# Alim_Ticketing_Slave.net
KiCad netlist of a schematic drawn in Altium Designer
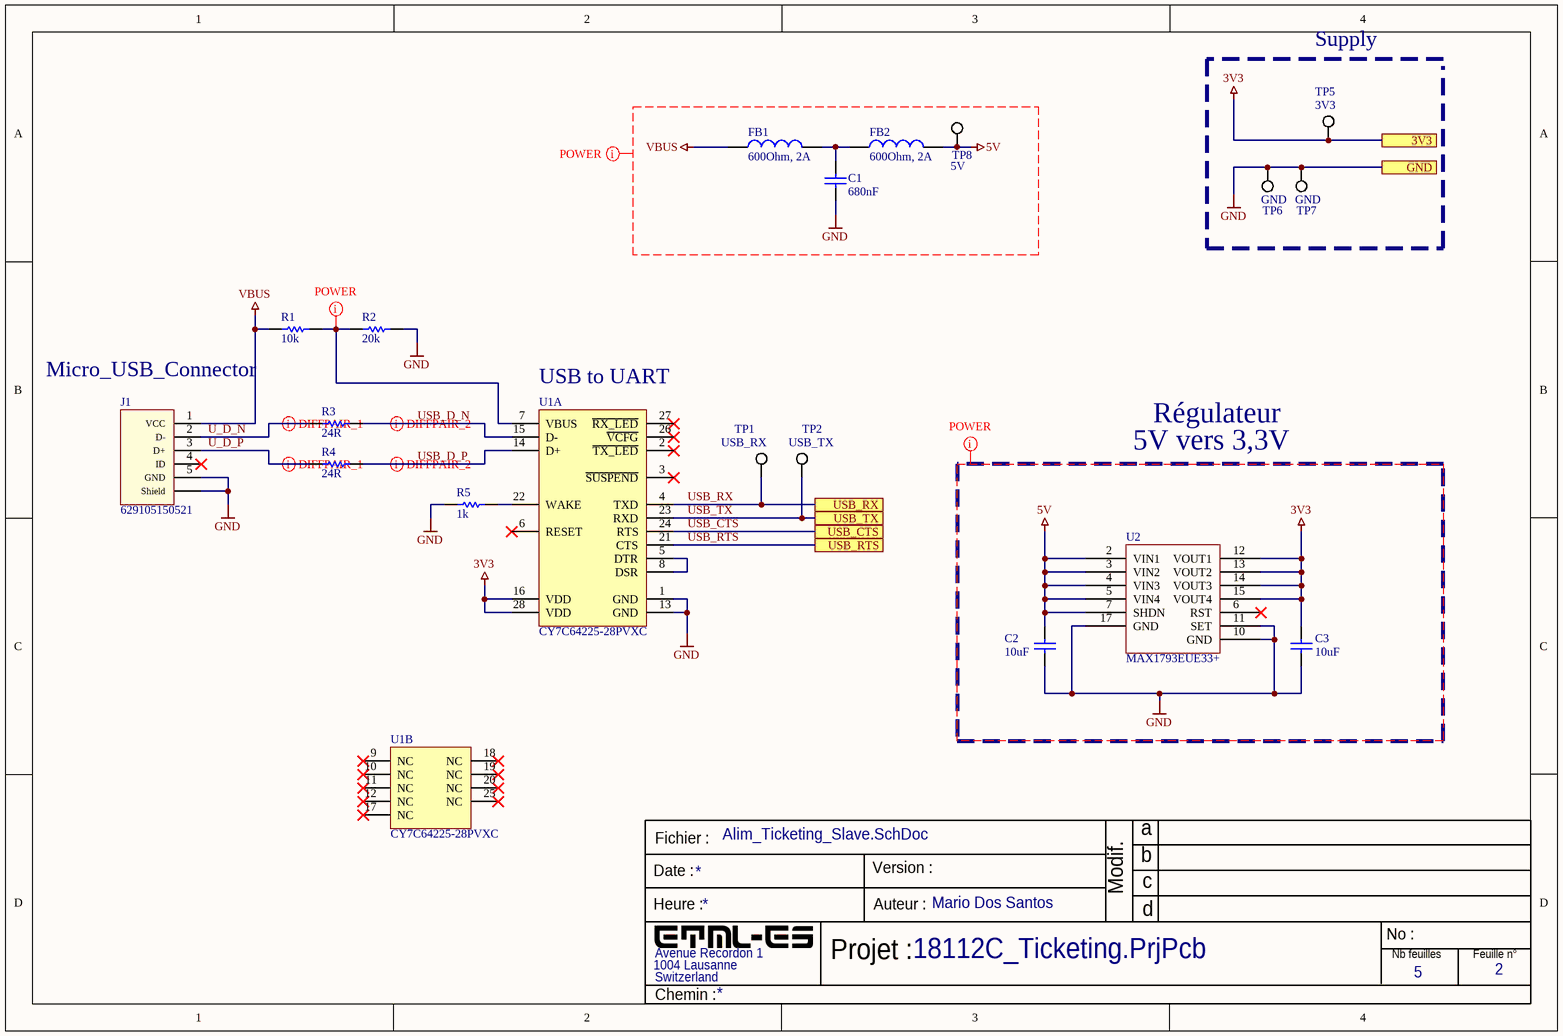
[diagram p0: Alim_Ticketing_Slave.SchDoc]

(export (version "E")
  (design (tool "Eeschema 10.0.6"))
  (components
    (comp (ref "C1")
      (value "680nF")
      (footprint "6-0805_N")
      (description "WCAP-CSGP General Purpose Ceramic Capacitors, size 0805, 100nF, +/-10%, 50VDC")
      (libsource (lib "VPA_v2b") (part "885012207098"))
    )
    (comp (ref "C2")
      (value "10uF")
      (footprint "6-0805_N")
      (description "Capacitor")
      (fields (field (name "PUBLISHER") "Altium Limited"))
      (libsource (lib "Miscellaneous Devices") (part "Cap"))
    )
    (comp (ref "C3")
      (value "10uF")
      (footprint "6-0805_N")
      (description "Capacitor")
      (fields (field (name "PUBLISHER") "Altium Limited"))
      (libsource (lib "Miscellaneous Devices") (part "Cap"))
    )
    (comp (ref "FB1")
      (value "600Ohm, 2A")
      (footprint "WE-CBF_0805_High Current")
      (description "WE-CBF SMT EMI Suppression Ferrite Bead, size 0805, 600Ohm, 2A")
      (fields (field (name "PART NUMBER") "742792040") (field (name "PUBLISHER") "Wurth Elektronik"))
      (libsource (lib "VPA_v2b") (part "742792040"))
    )
    (comp (ref "FB2")
      (value "600Ohm, 2A")
      (footprint "WE-CBF_0805_High Current")
      (description "WE-CBF SMT EMI Suppression Ferrite Bead, size 0805, 600Ohm, 2A")
      (fields (field (name "PART NUMBER") "742792040") (field (name "PUBLISHER") "Wurth Elektronik"))
      (libsource (lib "VPA_v2b") (part "742792040"))
    )
    (comp (ref "J1")
      (value "629105150521")
      (footprint "629105150521")
      (description "Micro USB 2.0 SMT Type B Horizontal 5 Contacts High Current WR-COM")
      (fields (field (name "PART NUMBER") "732-5960-1-ND") (field (name "PUBLISHER") "Wurth Elektronik"))
      (libsource (lib "PCB_Ticketing_Slave") (part "629105150521"))
    )
    (comp (ref "R1")
      (value "10k")
      (footprint "RESC0805(2012)_L")
      (description "100K 0.125W 5% 0805 (2012 Metric)  SMD")
      (fields (field (name "TOLERANCE") "5 %") (field (name "POWER") "0.125 W"))
      (libsource (lib "Altium Content Vault") (part "CMP-1013-00122-1"))
    )
    (comp (ref "R2")
      (value "20k")
      (footprint "RESC0805(2012)_L")
      (description "100K 0.125W 5% 0805 (2012 Metric)  SMD")
      (fields (field (name "TOLERANCE") "5 %") (field (name "POWER") "0.125 W"))
      (libsource (lib "Altium Content Vault") (part "CMP-1013-00122-1"))
    )
    (comp (ref "R3")
      (value "24R")
      (footprint "RESC0805(2012)_L")
      (description "100K 0.125W 5% 0805 (2012 Metric)  SMD")
      (fields (field (name "TOLERANCE") "5 %") (field (name "POWER") "0.125 W"))
      (libsource (lib "Altium Content Vault") (part "CMP-1013-00122-1"))
    )
    (comp (ref "R4")
      (value "24R")
      (footprint "RESC0805(2012)_L")
      (description "100K 0.125W 5% 0805 (2012 Metric)  SMD")
      (fields (field (name "TOLERANCE") "5 %") (field (name "POWER") "0.125 W"))
      (libsource (lib "Altium Content Vault") (part "CMP-1013-00122-1"))
    )
    (comp (ref "R5")
      (value "1k")
      (footprint "RESC0805(2012)_L")
      (description "100K 0.125W 5% 0805 (2012 Metric)  SMD")
      (fields (field (name "TOLERANCE") "5 %") (field (name "POWER") "0.125 W"))
      (libsource (lib "Altium Content Vault") (part "CMP-1013-00122-1"))
    )
    (comp (ref "TP1")
      (value "~")
      (footprint "KSTN-5019_V")
      (description "Test Point, 1 Position SMD, RoHS, Tape and Reel")
      (libsource (lib "Altium Content Vault") (part "TESTPOINT_WHITE"))
    )
    (comp (ref "TP2")
      (value "~")
      (footprint "KSTN-5019_V")
      (description "Test Point, 1 Position SMD, RoHS, Tape and Reel")
      (libsource (lib "Altium Content Vault") (part "TESTPOINT_WHITE"))
    )
    (comp (ref "TP5")
      (value "~")
      (footprint "KSTN-5019_V")
      (description "Test Point, 1 Position SMD, RoHS, Tape and Reel")
      (libsource (lib "Altium Content Vault") (part "TESTPOINT_WHITE"))
    )
    (comp (ref "TP6")
      (value "~")
      (footprint "KSTN-5019_V")
      (description "Test Point, 1 Position SMD, RoHS, Tape and Reel")
      (libsource (lib "Altium Content Vault") (part "TESTPOINT_WHITE"))
    )
    (comp (ref "TP7")
      (value "~")
      (footprint "KSTN-5019_V")
      (description "Test Point, 1 Position SMD, RoHS, Tape and Reel")
      (libsource (lib "Altium Content Vault") (part "TESTPOINT_WHITE"))
    )
    (comp (ref "TP8")
      (value "~")
      (footprint "KSTN-5019_V")
      (description "Test Point, 1 Position SMD, RoHS, Tape and Reel")
      (libsource (lib "Altium Content Vault") (part "TESTPOINT_WHITE"))
    )
    (comp (ref "U1")
      (value "CY7C64225-28PVXC")
      (footprint "CYP-PVX28_N")
      (description "USB-to-UART Bridge Controller, 3 to 5.25 V, 0 to 70 degC, 28-Pin SSOP (PVX28), Tube")
      (fields (field (name "MANUFACTURER") "Cypress") (field (name "PART NUMBER") "428-3158-ND"))
      (libsource (lib "PCB_Ticketing_Slave") (part "CMP-0967-00143-1"))
    )
    (comp (ref "U2")
      (value "MAX1793EUE33+")
      (footprint "TSOP65P640X110_HS-17N")
      (libsource (lib "2018A_CarteIoEscapeRoom_CAD") (part "MAX1793"))
    )
  )
  (nets
    (net (code "1") (name "/USB_CTS") (class "Default")
      (node (ref "U1") (pin "24") (pinfunction "RTS_24") (pintype "passive"))
    )
    (net (code "2") (name "/USB_D_N") (class "Default")
      (node (ref "R3") (pin "2") (pinfunction "2_2") (pintype "passive"))
      (node (ref "U1") (pin "15") (pinfunction "D-_15") (pintype "passive"))
    )
    (net (code "3") (name "/USB_D_P") (class "Default")
      (node (ref "R4") (pin "2") (pinfunction "2_2") (pintype "passive"))
      (node (ref "U1") (pin "14") (pinfunction "D+_14") (pintype "passive"))
    )
    (net (code "4") (name "/USB_RTS") (class "Default")
      (node (ref "U1") (pin "21") (pinfunction "CTS_21") (pintype "passive"))
    )
    (net (code "5") (name "/USB_RX") (class "Default")
      (node (ref "TP1") (pin "1") (pinfunction "1_1") (pintype "passive"))
      (node (ref "U1") (pin "4") (pinfunction "TXD_4") (pintype "passive"))
    )
    (net (code "6") (name "/USB_TX") (class "Default")
      (node (ref "TP2") (pin "1") (pinfunction "1_1") (pintype "passive"))
      (node (ref "U1") (pin "23") (pinfunction "RXD_23") (pintype "passive"))
    )
    (net (code "7") (name "/U_D_N") (class "Default")
      (node (ref "J1") (pin "2") (pinfunction "D-_2") (pintype "passive"))
      (node (ref "R3") (pin "1") (pinfunction "1_1") (pintype "passive"))
    )
    (net (code "8") (name "/U_D_P") (class "Default")
      (node (ref "J1") (pin "3") (pinfunction "D+_3") (pintype "passive"))
      (node (ref "R4") (pin "1") (pinfunction "1_1") (pintype "passive"))
    )
    (net (code "9") (name "3V3") (class "Default")
      (node (ref "C3") (pin "2") (pinfunction "2_2") (pintype "passive"))
      (node (ref "TP5") (pin "1") (pinfunction "1_1") (pintype "passive"))
      (node (ref "U1") (pin "16") (pinfunction "VDD_16") (pintype "passive"))
      (node (ref "U1") (pin "28") (pinfunction "VDD_28") (pintype "passive"))
      (node (ref "U2") (pin "12") (pinfunction "VOUT1_12") (pintype "passive"))
      (node (ref "U2") (pin "13") (pinfunction "VOUT2_13") (pintype "passive"))
      (node (ref "U2") (pin "14") (pinfunction "VOUT3_14") (pintype "passive"))
      (node (ref "U2") (pin "15") (pinfunction "VOUT4_15") (pintype "passive"))
    )
    (net (code "10") (name "5V") (class "Default")
      (node (ref "C2") (pin "1") (pinfunction "1_1") (pintype "passive"))
      (node (ref "FB2") (pin "2") (pinfunction "2_2") (pintype "passive"))
      (node (ref "TP8") (pin "1") (pinfunction "1_1") (pintype "passive"))
      (node (ref "U2") (pin "2") (pinfunction "VIN1_2") (pintype "passive"))
      (node (ref "U2") (pin "3") (pinfunction "VIN2_3") (pintype "passive"))
      (node (ref "U2") (pin "4") (pinfunction "VIN3_4") (pintype "passive"))
      (node (ref "U2") (pin "5") (pinfunction "VIN4_5") (pintype "passive"))
      (node (ref "U2") (pin "7") (pinfunction "SHDN_7") (pintype "passive"))
    )
    (net (code "11") (name "GND") (class "Default")
      (node (ref "C1") (pin "2") (pinfunction "2_2") (pintype "passive"))
      (node (ref "C2") (pin "2") (pinfunction "2_2") (pintype "passive"))
      (node (ref "C3") (pin "1") (pinfunction "1_1") (pintype "passive"))
      (node (ref "J1") (pin "5") (pinfunction "GND_5") (pintype "passive"))
      (node (ref "J1") (pin "Shell") (pinfunction "Shield_Shell") (pintype "passive"))
      (node (ref "R2") (pin "2") (pinfunction "2_2") (pintype "passive"))
      (node (ref "R5") (pin "2") (pinfunction "2_2") (pintype "passive"))
      (node (ref "TP6") (pin "1") (pinfunction "1_1") (pintype "passive"))
      (node (ref "TP7") (pin "1") (pinfunction "1_1") (pintype "passive"))
      (node (ref "U1") (pin "1") (pinfunction "GND_1") (pintype "passive"))
      (node (ref "U1") (pin "13") (pinfunction "GND_13") (pintype "passive"))
      (node (ref "U2") (pin "10") (pinfunction "GND_10") (pintype "power_in"))
      (node (ref "U2") (pin "11") (pinfunction "SET_11") (pintype "passive"))
      (node (ref "U2") (pin "17") (pinfunction "GND_17") (pintype "power_in"))
    )
    (net (code "12") (name "Net-(C1-Pad1)") (class "Default")
      (node (ref "C1") (pin "1") (pinfunction "1_1") (pintype "passive"))
      (node (ref "FB1") (pin "2") (pinfunction "2_2") (pintype "passive"))
      (node (ref "FB2") (pin "1") (pinfunction "1_1") (pintype "passive"))
    )
    (net (code "13") (name "Net-(U1A-DSR)") (class "Default")
      (node (ref "U1") (pin "5") (pinfunction "DTR_5") (pintype "passive"))
      (node (ref "U1") (pin "8") (pinfunction "DSR_8") (pintype "passive"))
    )
    (net (code "14") (name "Net-(U1A-VBUS)") (class "Default")
      (node (ref "R1") (pin "2") (pinfunction "2_2") (pintype "passive"))
      (node (ref "R2") (pin "1") (pinfunction "1_1") (pintype "passive"))
      (node (ref "U1") (pin "7") (pinfunction "VBUS_7") (pintype "passive"))
    )
    (net (code "15") (name "Net-(U1A-WAKE)") (class "Default")
      (node (ref "R5") (pin "1") (pinfunction "1_1") (pintype "passive"))
      (node (ref "U1") (pin "22") (pinfunction "WAKE_22") (pintype "passive"))
    )
    (net (code "16") (name "VBUS") (class "Default")
      (node (ref "FB1") (pin "1") (pinfunction "1_1") (pintype "passive"))
      (node (ref "J1") (pin "1") (pinfunction "VCC_1") (pintype "passive"))
      (node (ref "R1") (pin "1") (pinfunction "1_1") (pintype "passive"))
    )
    (net (code "17") (name "unconnected-(J1-ID-Pad4)") (class "Default")
      (node (ref "J1") (pin "4") (pinfunction "ID_4") (pintype "passive+no_connect"))
    )
    (net (code "18") (name "unconnected-(U1A-RESET-Pad6)") (class "Default")
      (node (ref "U1") (pin "6") (pinfunction "RESET_6") (pintype "passive+no_connect"))
    )
    (net (code "19") (name "unconnected-(U1A-~{RX_LED}-Pad27)") (class "Default")
      (node (ref "U1") (pin "27") (pinfunction "~{RX_LED}_27") (pintype "passive+no_connect"))
    )
    (net (code "20") (name "unconnected-(U1A-~{SUSPEND}-Pad3)") (class "Default")
      (node (ref "U1") (pin "3") (pinfunction "~{SUSPEND}_3") (pintype "passive+no_connect"))
    )
    (net (code "21") (name "unconnected-(U1A-~{TX_LED}-Pad2)") (class "Default")
      (node (ref "U1") (pin "2") (pinfunction "~{TX_LED}_2") (pintype "passive+no_connect"))
    )
    (net (code "22") (name "unconnected-(U1A-~{VCFG}-Pad26)") (class "Default")
      (node (ref "U1") (pin "26") (pinfunction "~{VCFG}_26") (pintype "passive+no_connect"))
    )
    (net (code "23") (name "unconnected-(U1B-NC-Pad9)") (class "Default")
      (node (ref "U1") (pin "9") (pinfunction "NC_9") (pintype "passive+no_connect"))
    )
    (net (code "24") (name "unconnected-(U1B-NC-Pad10)") (class "Default")
      (node (ref "U1") (pin "10") (pinfunction "NC_10") (pintype "passive+no_connect"))
    )
    (net (code "25") (name "unconnected-(U1B-NC-Pad11)") (class "Default")
      (node (ref "U1") (pin "11") (pinfunction "NC_11") (pintype "passive+no_connect"))
    )
    (net (code "26") (name "unconnected-(U1B-NC-Pad12)") (class "Default")
      (node (ref "U1") (pin "12") (pinfunction "NC_12") (pintype "passive+no_connect"))
    )
    (net (code "27") (name "unconnected-(U1B-NC-Pad17)") (class "Default")
      (node (ref "U1") (pin "17") (pinfunction "NC_17") (pintype "passive+no_connect"))
    )
    (net (code "28") (name "unconnected-(U1B-NC-Pad18)") (class "Default")
      (node (ref "U1") (pin "18") (pinfunction "NC_18") (pintype "passive+no_connect"))
    )
    (net (code "29") (name "unconnected-(U1B-NC-Pad19)") (class "Default")
      (node (ref "U1") (pin "19") (pinfunction "NC_19") (pintype "passive+no_connect"))
    )
    (net (code "30") (name "unconnected-(U1B-NC-Pad20)") (class "Default")
      (node (ref "U1") (pin "20") (pinfunction "NC_20") (pintype "passive+no_connect"))
    )
    (net (code "31") (name "unconnected-(U1B-NC-Pad25)") (class "Default")
      (node (ref "U1") (pin "25") (pinfunction "NC_25") (pintype "passive+no_connect"))
    )
    (net (code "32") (name "unconnected-(U2-RST-Pad6)") (class "Default")
      (node (ref "U2") (pin "6") (pinfunction "RST_6") (pintype "passive+no_connect"))
    )
  )
)
